# MPU.net
KiCad netlist of a schematic drawn in Altium Designer
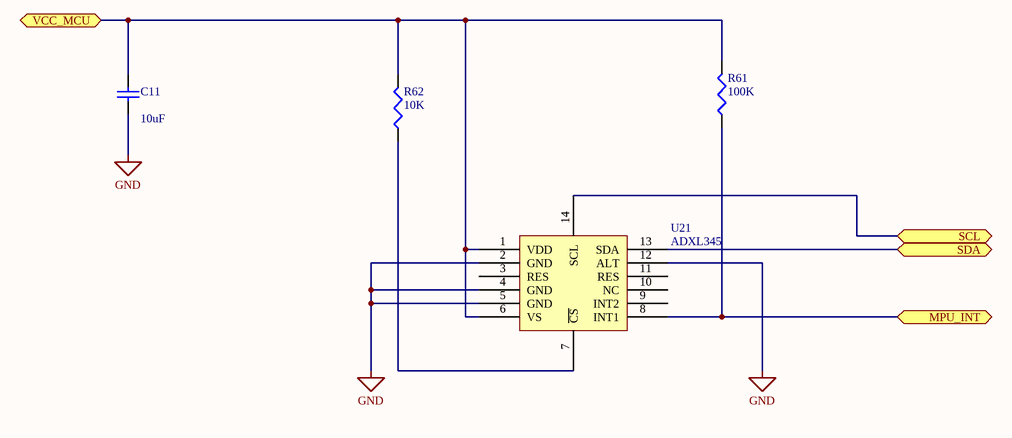
[diagram p0: MPU.SchDoc]

(export (version "E")
  (design (tool "Eeschema 10.0.6"))
  (components
    (comp (ref "C11")
      (value "10uF")
      (footprint "clock:0603")
      (description "Capacitor (Semiconductor SIM Model)")
      (fields (field (name "Comment") "Cap Semi") (field (name "PUBLISHER") "Altium Limited"))
      (libsource (lib "Miscellaneous Devices") (part "Cap Semi"))
    )
    (comp (ref "R61")
      (value "100K")
      (footprint "clock:0603")
      (description "Resistor")
      (fields (field (name "Comment") "Res3") (field (name "PUBLISHER") "Altium Limited"))
      (libsource (lib "Miscellaneous Devices") (part "Res3"))
    )
    (comp (ref "R62")
      (value "10K")
      (footprint "clock:0603")
      (description "Resistor")
      (fields (field (name "Comment") "Res3") (field (name "PUBLISHER") "Altium Limited"))
      (libsource (lib "Miscellaneous Devices") (part "Res3"))
    )
    (comp (ref "U21") (value "ADXL345") (footprint "clock:ALX") (libsource (lib "clock") (part "ADXL345")))
  )
  (nets
    (net (code "1") (name "/MPU_INT") (class "Default")
      (node (ref "R61") (pin "1") (pinfunction "1_1") (pintype "passive"))
      (node (ref "U21") (pin "8") (pinfunction "INT1_8") (pintype "passive"))
    )
    (net (code "2") (name "/SCL") (class "Default")
      (node (ref "U21") (pin "14") (pinfunction "SCL_14") (pintype "passive"))
    )
    (net (code "3") (name "/SDA") (class "Default")
      (node (ref "U21") (pin "13") (pinfunction "SDA_13") (pintype "passive"))
    )
    (net (code "4") (name "/VCC_MCU") (class "Default")
      (node (ref "C11") (pin "2") (pinfunction "2_2") (pintype "passive"))
      (node (ref "R61") (pin "2") (pinfunction "2_2") (pintype "passive"))
      (node (ref "R62") (pin "2") (pinfunction "2_2") (pintype "passive"))
      (node (ref "U21") (pin "1") (pinfunction "VDD_1") (pintype "passive"))
      (node (ref "U21") (pin "6") (pinfunction "VS_6") (pintype "passive"))
    )
    (net (code "5") (name "GND") (class "Default")
      (node (ref "C11") (pin "1") (pinfunction "1_1") (pintype "passive"))
      (node (ref "U21") (pin "12") (pinfunction "ALT_12") (pintype "passive"))
      (node (ref "U21") (pin "2") (pinfunction "GND_2") (pintype "passive"))
      (node (ref "U21") (pin "4") (pinfunction "GND_4") (pintype "passive"))
      (node (ref "U21") (pin "5") (pinfunction "GND_5") (pintype "passive"))
    )
    (net (code "6") (name "Net-(U21-~{CS})") (class "Default")
      (node (ref "R62") (pin "1") (pinfunction "1_1") (pintype "passive"))
      (node (ref "U21") (pin "7") (pinfunction "~{CS}_7") (pintype "passive"))
    )
    (net (code "7") (name "unconnected-(U21-INT2-Pad9)") (class "Default")
      (node (ref "U21") (pin "9") (pinfunction "INT2_9") (pintype "passive"))
    )
    (net (code "8") (name "unconnected-(U21-NC-Pad10)") (class "Default")
      (node (ref "U21") (pin "10") (pinfunction "NC_10") (pintype "passive"))
    )
    (net (code "9") (name "unconnected-(U21-RES-Pad3)") (class "Default")
      (node (ref "U21") (pin "3") (pinfunction "RES_3") (pintype "passive"))
    )
    (net (code "10") (name "unconnected-(U21-RES-Pad11)") (class "Default")
      (node (ref "U21") (pin "11") (pinfunction "RES_11") (pintype "passive"))
    )
  )
)
